# ArduOSD_Simple2222.net
KiCad netlist of a schematic drawn in EAGLE
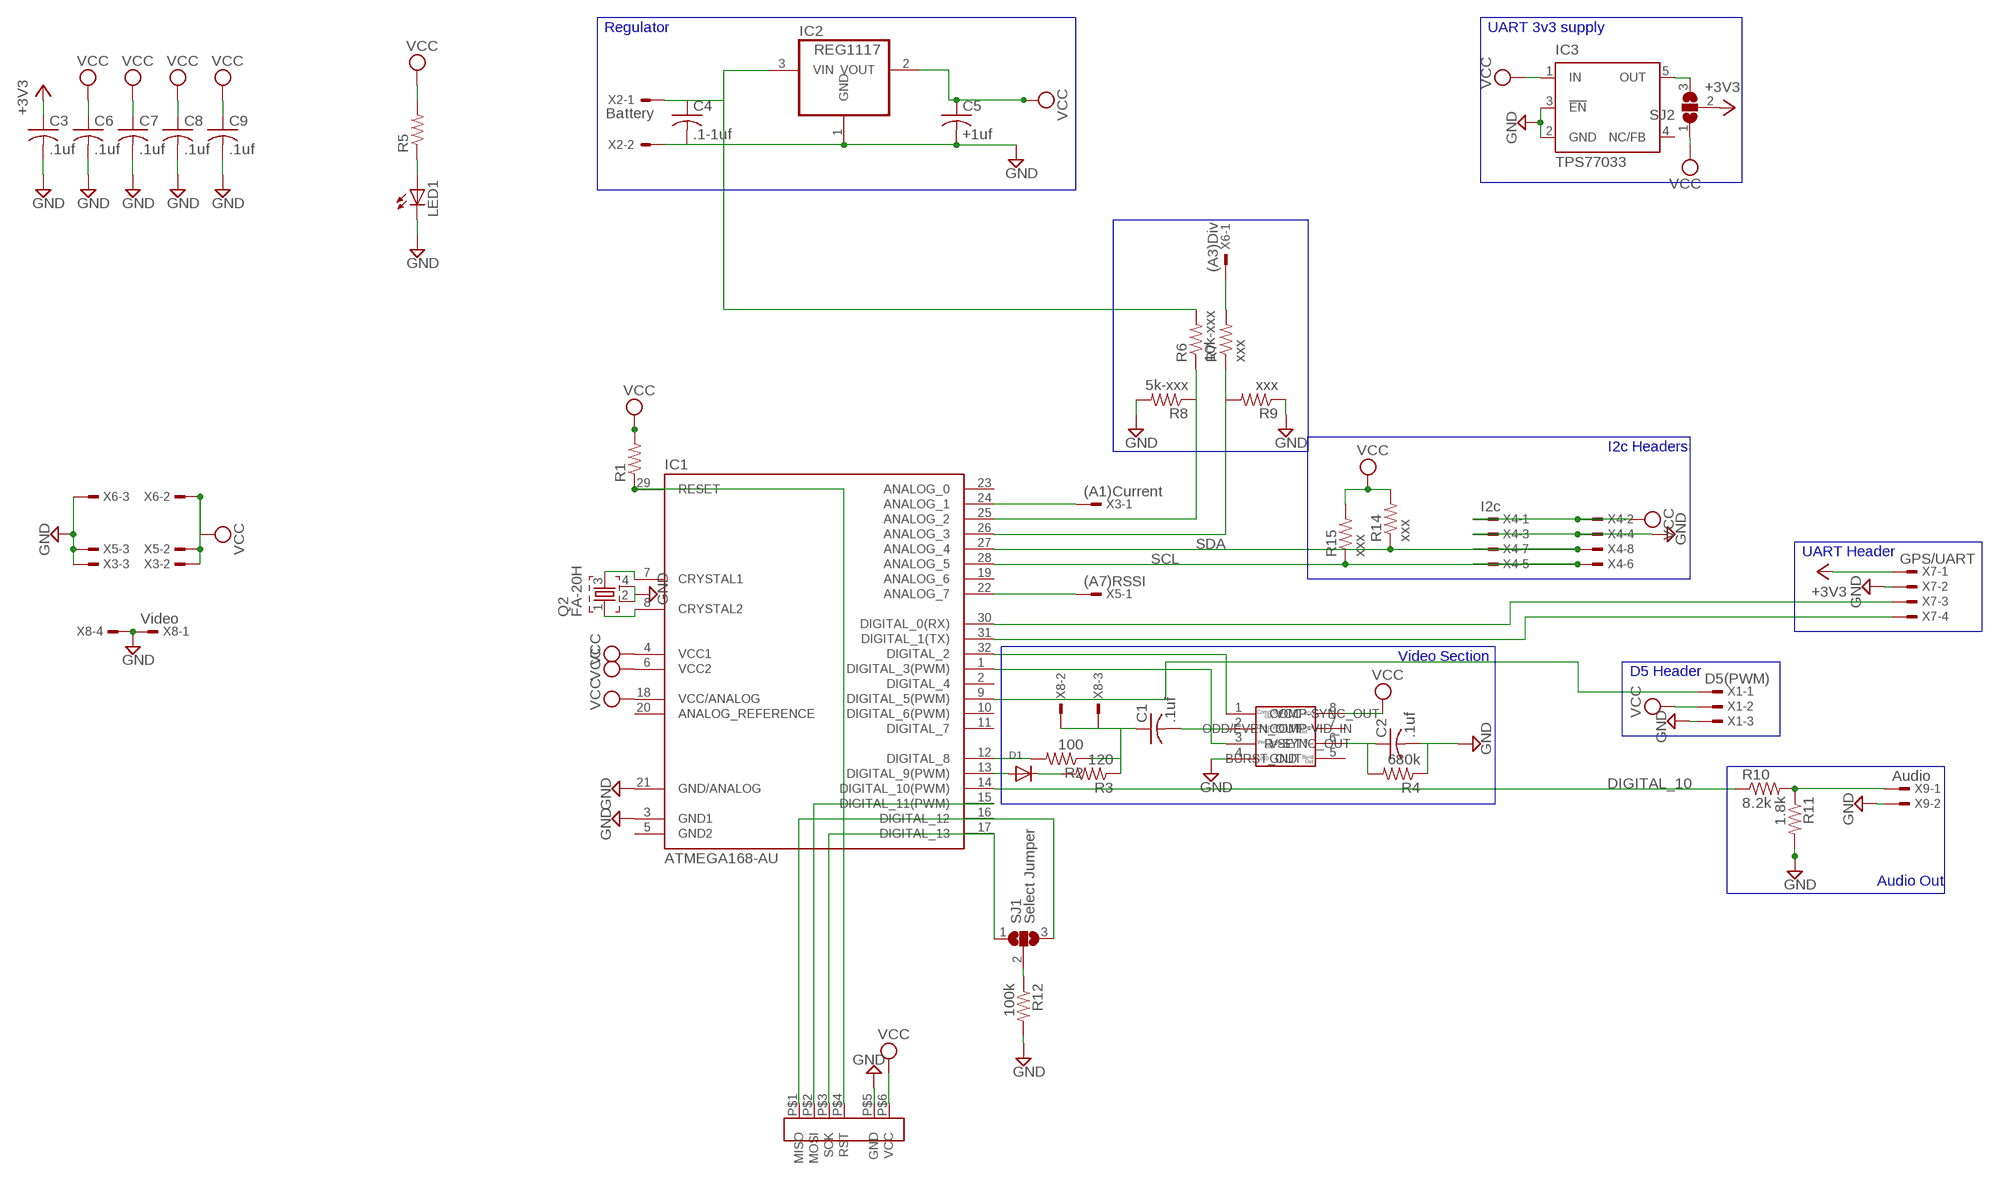
[diagram p0: schematic, sheet 1]

(export (version "E")
  (design (tool "Eeschema 10.0.6"))
  (components
    (comp (ref "C1")
      (value ".1uf")
      (footprint "eagle-import:C0805K")
      (libsource (lib "eagle-import") (part "C-USC0805K"))
    )
    (comp (ref "C2")
      (value ".1uf")
      (footprint "eagle-import:C0805K")
      (libsource (lib "eagle-import") (part "C-USC0805K"))
    )
    (comp (ref "C3")
      (value ".1uf")
      (footprint "eagle-import:C0805K")
      (libsource (lib "eagle-import") (part "C-USC0805K"))
    )
    (comp (ref "C4")
      (value ".1-1uf")
      (footprint "eagle-import:C0805K")
      (libsource (lib "eagle-import") (part "C-USC0805K"))
    )
    (comp (ref "C5")
      (value "+1uf")
      (footprint "eagle-import:C0805K")
      (libsource (lib "eagle-import") (part "C-USC0805K"))
    )
    (comp (ref "C6")
      (value ".1uf")
      (footprint "eagle-import:C0805K")
      (libsource (lib "eagle-import") (part "C-USC0805K"))
    )
    (comp (ref "C7")
      (value ".1uf")
      (footprint "eagle-import:C0805K")
      (libsource (lib "eagle-import") (part "C-USC0805K"))
    )
    (comp (ref "C8")
      (value ".1uf")
      (footprint "eagle-import:C0805K")
      (libsource (lib "eagle-import") (part "C-USC0805K"))
    )
    (comp (ref "C9")
      (value ".1uf")
      (footprint "eagle-import:C0805K")
      (libsource (lib "eagle-import") (part "C-USC0805K"))
    )
    (comp (ref "D1")
      (value "DIODESOT23_WAVE")
      (footprint "eagle-import:SOT23-W")
      (libsource (lib "eagle-import") (part "DIODESOT23_WAVE"))
    )
    (comp (ref "IC1")
      (value "ATMEGA168-AU")
      (footprint "eagle-import:TQFP32-08")
      (libsource (lib "eagle-import") (part "ATMEGA168-AU"))
    )
    (comp (ref "IC2")
      (value "REG1117")
      (footprint "eagle-import:SOT223")
      (libsource (lib "eagle-import") (part "REG1117"))
    )
    (comp (ref "IC3")
      (value "TPS77033")
      (footprint "eagle-import:SOT23-DBV")
      (fields (field (name "MF") "TEXAS INSTRUMENTS") (field (name "MPN") "TPS77033DBVT"))
      (libsource (lib "eagle-import") (part "TPS77033"))
    )
    (comp (ref "LED1")
      (value "LEDCHIP-LED0805")
      (footprint "eagle-import:CHIP-LED0805")
      (libsource (lib "eagle-import") (part "LEDCHIP-LED0805"))
    )
    (comp (ref "LM1881")
      (value "LM1881SO08")
      (footprint "eagle-import:SO08")
      (libsource (lib "eagle-import") (part "LM1881SO08"))
    )
    (comp (ref "Q2")
      (value "FA-20H")
      (footprint "eagle-import:FA-20H")
      (libsource (lib "eagle-import") (part "FA-20H"))
    )
    (comp (ref "R1")
      (value "R-US_R0805")
      (footprint "eagle-import:R0805")
      (libsource (lib "eagle-import") (part "R-US_R0805"))
    )
    (comp (ref "R2")
      (value "100")
      (footprint "eagle-import:R0805")
      (libsource (lib "eagle-import") (part "R-US_R0805"))
    )
    (comp (ref "R3")
      (value "120")
      (footprint "eagle-import:R0805")
      (libsource (lib "eagle-import") (part "R-US_R0805"))
    )
    (comp (ref "R4")
      (value "680k")
      (footprint "eagle-import:R0805")
      (libsource (lib "eagle-import") (part "R-US_R0805"))
    )
    (comp (ref "R5")
      (value "R-US_R0805")
      (footprint "eagle-import:R0805")
      (libsource (lib "eagle-import") (part "R-US_R0805"))
    )
    (comp (ref "R6")
      (value "10k-xxx")
      (footprint "eagle-import:R0805")
      (libsource (lib "eagle-import") (part "R-US_R0805"))
    )
    (comp (ref "R7")
      (value "xxx")
      (footprint "eagle-import:R0805")
      (libsource (lib "eagle-import") (part "R-US_R0805"))
    )
    (comp (ref "R8")
      (value "5k-xxx")
      (footprint "eagle-import:R0805")
      (libsource (lib "eagle-import") (part "R-US_R0805"))
    )
    (comp (ref "R9")
      (value "xxx")
      (footprint "eagle-import:R0805")
      (libsource (lib "eagle-import") (part "R-US_R0805"))
    )
    (comp (ref "R10")
      (value "8.2k")
      (footprint "eagle-import:R0805")
      (libsource (lib "eagle-import") (part "R-US_R0805"))
    )
    (comp (ref "R11")
      (value "1.8k")
      (footprint "eagle-import:R0805")
      (libsource (lib "eagle-import") (part "R-US_R0805"))
    )
    (comp (ref "R12")
      (value "100k")
      (footprint "eagle-import:R0805")
      (libsource (lib "eagle-import") (part "R-US_R0805"))
    )
    (comp (ref "R14")
      (value "xxx")
      (footprint "eagle-import:R0805")
      (libsource (lib "eagle-import") (part "R-US_R0805"))
    )
    (comp (ref "R15")
      (value "xxx")
      (footprint "eagle-import:R0805")
      (libsource (lib "eagle-import") (part "R-US_R0805"))
    )
    (comp (ref "SJ1")
      (value "Select Jumper")
      (footprint "eagle-import:SJ_2")
      (libsource (lib "eagle-import") (part "SJ2W"))
    )
    (comp (ref "SJ2")
      (value "SJ2W")
      (footprint "eagle-import:SJ_2")
      (libsource (lib "eagle-import") (part "SJ2W"))
    )
    (comp (ref "U$1")
      (value "LIN_ISP")
      (footprint "eagle-import:LINEAR_ISP")
      (libsource (lib "eagle-import") (part "LIN_ISP"))
    )
    (comp (ref "X1")
      (value "D5(PWM)")
      (footprint "eagle-import:TSW-103-02-S-S")
      (fields (field (name "OC_FARNELL") "unknown") (field (name "OC_NEWARK") "unknown"))
      (libsource (lib "eagle-import") (part "TSW-103-02-S-S"))
    )
    (comp (ref "X2")
      (value "Battery")
      (footprint "eagle-import:22-23-2021")
      (fields (field (name "MF") "MOLEX") (field (name "MPN") "22-23-2021"))
      (libsource (lib "eagle-import") (part "22-23-2021"))
    )
    (comp (ref "X3")
      (value "(A1)Current")
      (footprint "eagle-import:TSW-103-02-S-S")
      (libsource (lib "eagle-import") (part "TSW-103-02-S-S"))
    )
    (comp (ref "X4")
      (value "I2c")
      (footprint "eagle-import:TSW-104-02-S-D-RA")
      (libsource (lib "eagle-import") (part "TSW-104-02-S-D-RA"))
    )
    (comp (ref "X5")
      (value "(A7)RSSI")
      (footprint "eagle-import:TSW-103-02-S-S")
      (libsource (lib "eagle-import") (part "TSW-103-02-S-S"))
    )
    (comp (ref "X6")
      (value "(A3)Div")
      (footprint "eagle-import:TSW-103-02-S-S")
      (fields (field (name "OC_FARNELL") "unknown") (field (name "OC_NEWARK") "unknown"))
      (libsource (lib "eagle-import") (part "TSW-103-02-S-S"))
    )
    (comp (ref "X7")
      (value "GPS/UART")
      (footprint "eagle-import:TSW-104-02-S-S-RA")
      (libsource (lib "eagle-import") (part "TSW-104-02-S-S-RA"))
    )
    (comp (ref "X8")
      (value "Video")
      (footprint "eagle-import:TSW-104-02-S-S-RA")
      (libsource (lib "eagle-import") (part "TSW-104-02-S-S-RA"))
    )
    (comp (ref "X9")
      (value "Audio")
      (footprint "eagle-import:TSW-102-02-S-S-RA")
      (fields (field (name "OC_FARNELL") "unknown") (field (name "OC_NEWARK") "unknown"))
      (libsource (lib "eagle-import") (part "TSW-102-02-S-S-RA"))
    )
  )
  (nets
    (net (code "1") (name "+3V3") (class "Default")
      (node (ref "C3") (pin "1") (pinfunction "1_1") (pintype "passive"))
      (node (ref "SJ2") (pin "2") (pinfunction "2_2") (pintype "passive"))
      (node (ref "X7") (pin "1") (pinfunction "1_1") (pintype "passive"))
    )
    (net (code "2") (name "/DIGITAL_10") (class "Default")
      (node (ref "IC1") (pin "14") (pinfunction "DIGITAL_10(PWM)_14") (pintype "bidirectional"))
      (node (ref "R10") (pin "1") (pinfunction "1_1") (pintype "passive"))
    )
    (net (code "3") (name "/GND2") (class "Default")
      (node (ref "IC1") (pin "5") (pinfunction "GND2_5") (pintype "power_in"))
    )
    (net (code "4") (name "/SCL") (class "Default")
      (node (ref "IC1") (pin "28") (pinfunction "ANALOG_5_28") (pintype "bidirectional"))
      (node (ref "R15") (pin "1") (pinfunction "1_1") (pintype "passive"))
      (node (ref "X4") (pin "5") (pinfunction "1_5") (pintype "passive"))
      (node (ref "X4") (pin "6") (pinfunction "1_6") (pintype "passive"))
    )
    (net (code "5") (name "/SDA") (class "Default")
      (node (ref "IC1") (pin "27") (pinfunction "ANALOG_4_27") (pintype "bidirectional"))
      (node (ref "R14") (pin "1") (pinfunction "1_1") (pintype "passive"))
      (node (ref "X4") (pin "7") (pinfunction "1_7") (pintype "passive"))
      (node (ref "X4") (pin "8") (pinfunction "1_8") (pintype "passive"))
    )
    (net (code "6") (name "GND") (class "Default")
      (node (ref "C2") (pin "2") (pinfunction "2_2") (pintype "passive"))
      (node (ref "C3") (pin "2") (pinfunction "2_2") (pintype "passive"))
      (node (ref "C4") (pin "2") (pinfunction "2_2") (pintype "passive"))
      (node (ref "C5") (pin "2") (pinfunction "2_2") (pintype "passive"))
      (node (ref "C6") (pin "2") (pinfunction "2_2") (pintype "passive"))
      (node (ref "C7") (pin "2") (pinfunction "2_2") (pintype "passive"))
      (node (ref "C8") (pin "2") (pinfunction "2_2") (pintype "passive"))
      (node (ref "C9") (pin "2") (pinfunction "2_2") (pintype "passive"))
      (node (ref "IC1") (pin "21") (pinfunction "GND/ANALOG_21") (pintype "power_in"))
      (node (ref "IC1") (pin "3") (pinfunction "GND1_3") (pintype "power_in"))
      (node (ref "IC2") (pin "1") (pinfunction "GND_1") (pintype "power_in"))
      (node (ref "IC3") (pin "2") (pinfunction "GND_2") (pintype "power_in"))
      (node (ref "IC3") (pin "3") (pinfunction "~{EN}_3") (pintype "input"))
      (node (ref "LED1") (pin "C") (pinfunction "C_C") (pintype "passive"))
      (node (ref "LM1881") (pin "4") (pinfunction "GND_4") (pintype "bidirectional"))
      (node (ref "Q2") (pin "2") (pinfunction "2_2") (pintype "passive"))
      (node (ref "Q2") (pin "4") (pinfunction "4_4") (pintype "passive"))
      (node (ref "R11") (pin "2") (pinfunction "2_2") (pintype "passive"))
      (node (ref "R12") (pin "2") (pinfunction "2_2") (pintype "passive"))
      (node (ref "R4") (pin "1") (pinfunction "1_1") (pintype "passive"))
      (node (ref "R8") (pin "2") (pinfunction "2_2") (pintype "passive"))
      (node (ref "R9") (pin "1") (pinfunction "1_1") (pintype "passive"))
      (node (ref "U$1") (pin "P$5") (pinfunction "GND_P$5") (pintype "bidirectional"))
      (node (ref "X1") (pin "3") (pinfunction "1_3") (pintype "passive"))
      (node (ref "X2") (pin "2") (pinfunction "S_2") (pintype "passive"))
      (node (ref "X3") (pin "3") (pinfunction "1_3") (pintype "passive"))
      (node (ref "X4") (pin "3") (pinfunction "1_3") (pintype "passive"))
      (node (ref "X4") (pin "4") (pinfunction "1_4") (pintype "passive"))
      (node (ref "X5") (pin "3") (pinfunction "1_3") (pintype "passive"))
      (node (ref "X6") (pin "3") (pinfunction "1_3") (pintype "passive"))
      (node (ref "X7") (pin "2") (pinfunction "1_2") (pintype "passive"))
      (node (ref "X8") (pin "1") (pinfunction "1_1") (pintype "passive"))
      (node (ref "X8") (pin "4") (pinfunction "1_4") (pintype "passive"))
      (node (ref "X9") (pin "2") (pinfunction "1_2") (pintype "passive"))
    )
    (net (code "7") (name "Net-(D1-A)") (class "Default")
      (node (ref "D1") (pin "1") (pinfunction "A_1") (pintype "passive"))
      (node (ref "IC1") (pin "13") (pinfunction "DIGITAL_9(PWM)_13") (pintype "bidirectional"))
    )
    (net (code "8") (name "Net-(D1-C)") (class "Default")
      (node (ref "D1") (pin "3") (pinfunction "C_3") (pintype "passive"))
      (node (ref "R3") (pin "2") (pinfunction "2_2") (pintype "passive"))
    )
    (net (code "9") (name "Net-(IC1-ANALOG_1)") (class "Default")
      (node (ref "IC1") (pin "24") (pinfunction "ANALOG_1_24") (pintype "bidirectional"))
      (node (ref "X3") (pin "1") (pinfunction "1_1") (pintype "passive"))
    )
    (net (code "10") (name "Net-(IC1-ANALOG_2)") (class "Default")
      (node (ref "IC1") (pin "25") (pinfunction "ANALOG_2_25") (pintype "bidirectional"))
      (node (ref "R6") (pin "1") (pinfunction "1_1") (pintype "passive"))
      (node (ref "R8") (pin "1") (pinfunction "1_1") (pintype "passive"))
    )
    (net (code "11") (name "Net-(IC1-ANALOG_3)") (class "Default")
      (node (ref "IC1") (pin "26") (pinfunction "ANALOG_3_26") (pintype "bidirectional"))
      (node (ref "R7") (pin "1") (pinfunction "1_1") (pintype "passive"))
      (node (ref "R9") (pin "2") (pinfunction "2_2") (pintype "passive"))
    )
    (net (code "12") (name "Net-(IC1-ANALOG_7)") (class "Default")
      (node (ref "IC1") (pin "22") (pinfunction "ANALOG_7_22") (pintype "passive"))
      (node (ref "X5") (pin "1") (pinfunction "1_1") (pintype "passive"))
    )
    (net (code "13") (name "Net-(IC1-CRYSTAL1)") (class "Default")
      (node (ref "IC1") (pin "7") (pinfunction "CRYSTAL1_7") (pintype "bidirectional"))
      (node (ref "Q2") (pin "3") (pinfunction "3_3") (pintype "passive"))
    )
    (net (code "14") (name "Net-(IC1-CRYSTAL2)") (class "Default")
      (node (ref "IC1") (pin "8") (pinfunction "CRYSTAL2_8") (pintype "bidirectional"))
      (node (ref "Q2") (pin "1") (pinfunction "1_1") (pintype "passive"))
    )
    (net (code "15") (name "Net-(IC1-DIGITAL_0(RX))") (class "Default")
      (node (ref "IC1") (pin "30") (pinfunction "DIGITAL_0(RX)_30") (pintype "bidirectional"))
      (node (ref "X7") (pin "3") (pinfunction "1_3") (pintype "passive"))
    )
    (net (code "16") (name "Net-(IC1-DIGITAL_1(TX))") (class "Default")
      (node (ref "IC1") (pin "31") (pinfunction "DIGITAL_1(TX)_31") (pintype "bidirectional"))
      (node (ref "X7") (pin "4") (pinfunction "1_4") (pintype "passive"))
    )
    (net (code "17") (name "Net-(IC1-DIGITAL_2)") (class "Default")
      (node (ref "IC1") (pin "32") (pinfunction "DIGITAL_2_32") (pintype "bidirectional"))
      (node (ref "LM1881") (pin "1") (pinfunction "COMP-SYNC_OUT_1") (pintype "bidirectional"))
    )
    (net (code "18") (name "Net-(IC1-DIGITAL_3(PWM))") (class "Default")
      (node (ref "IC1") (pin "1") (pinfunction "DIGITAL_3(PWM)_1") (pintype "bidirectional"))
      (node (ref "LM1881") (pin "3") (pinfunction "V-SYNC_OUT_3") (pintype "bidirectional"))
    )
    (net (code "19") (name "Net-(IC1-DIGITAL_5(PWM))") (class "Default")
      (node (ref "IC1") (pin "9") (pinfunction "DIGITAL_5(PWM)_9") (pintype "bidirectional"))
      (node (ref "X1") (pin "1") (pinfunction "1_1") (pintype "passive"))
    )
    (net (code "20") (name "Net-(IC1-DIGITAL_8)") (class "Default")
      (node (ref "IC1") (pin "12") (pinfunction "DIGITAL_8_12") (pintype "bidirectional"))
      (node (ref "R2") (pin "2") (pinfunction "2_2") (pintype "passive"))
    )
    (net (code "21") (name "Net-(IC1-DIGITAL_11(PWM))") (class "Default")
      (node (ref "IC1") (pin "15") (pinfunction "DIGITAL_11(PWM)_15") (pintype "bidirectional"))
      (node (ref "U$1") (pin "P$2") (pinfunction "MOSI_P$2") (pintype "bidirectional"))
    )
    (net (code "22") (name "Net-(IC1-DIGITAL_12)") (class "Default")
      (node (ref "IC1") (pin "16") (pinfunction "DIGITAL_12_16") (pintype "bidirectional"))
      (node (ref "SJ1") (pin "3") (pinfunction "3_3") (pintype "passive"))
      (node (ref "U$1") (pin "P$1") (pinfunction "MISO_P$1") (pintype "bidirectional"))
    )
    (net (code "23") (name "Net-(IC1-DIGITAL_13)") (class "Default")
      (node (ref "IC1") (pin "17") (pinfunction "DIGITAL_13_17") (pintype "bidirectional"))
      (node (ref "SJ1") (pin "1") (pinfunction "1_1") (pintype "passive"))
      (node (ref "U$1") (pin "P$3") (pinfunction "SCK_P$3") (pintype "bidirectional"))
    )
    (net (code "24") (name "Net-(IC1-RESET)") (class "Default")
      (node (ref "IC1") (pin "29") (pinfunction "RESET_29") (pintype "bidirectional"))
      (node (ref "R1") (pin "1") (pinfunction "1_1") (pintype "passive"))
      (node (ref "U$1") (pin "P$4") (pinfunction "RST_P$4") (pintype "bidirectional"))
    )
    (net (code "25") (name "Net-(IC2-VIN)") (class "Default")
      (node (ref "C4") (pin "1") (pinfunction "1_1") (pintype "passive"))
      (node (ref "IC2") (pin "3") (pinfunction "VIN_3") (pintype "input"))
      (node (ref "R6") (pin "2") (pinfunction "2_2") (pintype "passive"))
      (node (ref "X2") (pin "1") (pinfunction "S_1") (pintype "passive"))
    )
    (net (code "26") (name "Net-(IC3-OUT)") (class "Default")
      (node (ref "IC3") (pin "5") (pinfunction "OUT_5") (pintype "passive"))
      (node (ref "SJ2") (pin "3") (pinfunction "3_3") (pintype "passive"))
    )
    (net (code "27") (name "Net-(LED1-PadA)") (class "Default")
      (node (ref "LED1") (pin "A") (pinfunction "A_A") (pintype "passive"))
      (node (ref "R5") (pin "1") (pinfunction "1_1") (pintype "passive"))
    )
    (net (code "28") (name "Net-(LM1881-COMP-VID_IN)") (class "Default")
      (node (ref "C1") (pin "2") (pinfunction "2_2") (pintype "passive"))
      (node (ref "LM1881") (pin "2") (pinfunction "COMP-VID_IN_2") (pintype "bidirectional"))
    )
    (net (code "29") (name "Net-(LM1881-R-SET)") (class "Default")
      (node (ref "C2") (pin "1") (pinfunction "1_1") (pintype "passive"))
      (node (ref "LM1881") (pin "6") (pinfunction "R-SET_6") (pintype "bidirectional"))
      (node (ref "R4") (pin "2") (pinfunction "2_2") (pintype "passive"))
    )
    (net (code "30") (name "Net-(R7-Pad2)") (class "Default")
      (node (ref "R7") (pin "2") (pinfunction "2_2") (pintype "passive"))
      (node (ref "X6") (pin "1") (pinfunction "1_1") (pintype "passive"))
    )
    (net (code "31") (name "Net-(R10-Pad2)") (class "Default")
      (node (ref "R10") (pin "2") (pinfunction "2_2") (pintype "passive"))
      (node (ref "R11") (pin "1") (pinfunction "1_1") (pintype "passive"))
      (node (ref "X9") (pin "1") (pinfunction "1_1") (pintype "passive"))
    )
    (net (code "32") (name "Net-(R12-Pad1)") (class "Default")
      (node (ref "R12") (pin "1") (pinfunction "1_1") (pintype "passive"))
      (node (ref "SJ1") (pin "2") (pinfunction "2_2") (pintype "passive"))
    )
    (net (code "33") (name "Net-(X8B-1)") (class "Default")
      (node (ref "C1") (pin "1") (pinfunction "1_1") (pintype "passive"))
      (node (ref "R2") (pin "1") (pinfunction "1_1") (pintype "passive"))
      (node (ref "R3") (pin "1") (pinfunction "1_1") (pintype "passive"))
      (node (ref "X8") (pin "2") (pinfunction "1_2") (pintype "passive"))
      (node (ref "X8") (pin "3") (pinfunction "1_3") (pintype "passive"))
    )
    (net (code "34") (name "VCC") (class "Default")
      (node (ref "C5") (pin "1") (pinfunction "1_1") (pintype "passive"))
      (node (ref "C6") (pin "1") (pinfunction "1_1") (pintype "passive"))
      (node (ref "C7") (pin "1") (pinfunction "1_1") (pintype "passive"))
      (node (ref "C8") (pin "1") (pinfunction "1_1") (pintype "passive"))
      (node (ref "C9") (pin "1") (pinfunction "1_1") (pintype "passive"))
      (node (ref "IC1") (pin "18") (pinfunction "VCC/ANALOG_18") (pintype "passive"))
      (node (ref "IC1") (pin "4") (pinfunction "VCC1_4") (pintype "power_in"))
      (node (ref "IC1") (pin "6") (pinfunction "VCC2_6") (pintype "power_in"))
      (node (ref "IC2") (pin "2") (pinfunction "VOUT_2") (pintype "output"))
      (node (ref "IC3") (pin "1") (pinfunction "IN_1") (pintype "input"))
      (node (ref "LM1881") (pin "8") (pinfunction "VCC_8") (pintype "bidirectional"))
      (node (ref "R1") (pin "2") (pinfunction "2_2") (pintype "passive"))
      (node (ref "R14") (pin "2") (pinfunction "2_2") (pintype "passive"))
      (node (ref "R15") (pin "2") (pinfunction "2_2") (pintype "passive"))
      (node (ref "R5") (pin "2") (pinfunction "2_2") (pintype "passive"))
      (node (ref "SJ2") (pin "1") (pinfunction "1_1") (pintype "passive"))
      (node (ref "U$1") (pin "P$6") (pinfunction "VCC_P$6") (pintype "bidirectional"))
      (node (ref "X1") (pin "2") (pinfunction "1_2") (pintype "passive"))
      (node (ref "X3") (pin "2") (pinfunction "1_2") (pintype "passive"))
      (node (ref "X4") (pin "1") (pinfunction "1_1") (pintype "passive"))
      (node (ref "X4") (pin "2") (pinfunction "1_2") (pintype "passive"))
      (node (ref "X5") (pin "2") (pinfunction "1_2") (pintype "passive"))
      (node (ref "X6") (pin "2") (pinfunction "1_2") (pintype "passive"))
    )
    (net (code "35") (name "unconnected-(IC1-ANALOG_0-Pad23)") (class "Default")
      (node (ref "IC1") (pin "23") (pinfunction "ANALOG_0_23") (pintype "bidirectional"))
    )
    (net (code "36") (name "unconnected-(IC1-ANALOG_6-Pad19)") (class "Default")
      (node (ref "IC1") (pin "19") (pinfunction "ANALOG_6_19") (pintype "passive"))
    )
    (net (code "37") (name "unconnected-(IC1-ANALOG_REFERENCE-Pad20)") (class "Default")
      (node (ref "IC1") (pin "20") (pinfunction "ANALOG_REFERENCE_20") (pintype "passive"))
    )
    (net (code "38") (name "unconnected-(IC1-DIGITAL_4-Pad2)") (class "Default")
      (node (ref "IC1") (pin "2") (pinfunction "DIGITAL_4_2") (pintype "bidirectional"))
    )
    (net (code "39") (name "unconnected-(IC1-DIGITAL_6(PWM)-Pad10)") (class "Default")
      (node (ref "IC1") (pin "10") (pinfunction "DIGITAL_6(PWM)_10") (pintype "bidirectional"))
    )
    (net (code "40") (name "unconnected-(IC1-DIGITAL_7-Pad11)") (class "Default")
      (node (ref "IC1") (pin "11") (pinfunction "DIGITAL_7_11") (pintype "bidirectional"))
    )
    (net (code "41") (name "unconnected-(IC3-NC{slash}FB-Pad4)") (class "Default")
      (node (ref "IC3") (pin "4") (pinfunction "NC/FB_4") (pintype "passive"))
    )
    (net (code "42") (name "unconnected-(LM1881-BURST_OUT-Pad5)") (class "Default")
      (node (ref "LM1881") (pin "5") (pinfunction "BURST_OUT_5") (pintype "bidirectional"))
    )
    (net (code "43") (name "unconnected-(LM1881-ODD{slash}EVEN_OUT-Pad7)") (class "Default")
      (node (ref "LM1881") (pin "7") (pinfunction "ODD/EVEN_OUT_7") (pintype "bidirectional"))
    )
  )
)
